# PowerSwitch_DiodeOr.net
KiCad netlist of a schematic drawn in Altium Designer
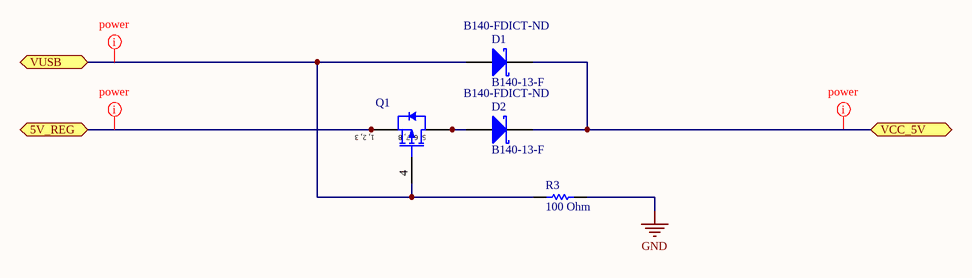
[diagram p0: PowerSwitch_DiodeOr.SchDoc]

(export (version "E")
  (design (tool "Eeschema 10.0.6"))
  (components
    (comp (ref "D1")
      (value "B140-13-F")
      (footprint "DIOD-B1X0-2_V")
      (description "Surface Mount Schottky Barrier Rectifier, 1 A, -65 to 150 degC, 2-Pin SMA, RoHS, Tape and Reel")
      (fields
        (field (name "MANUFACTURER") "DiodesIncorporated")
        (field (name "HOUSEPART") "YES")
        (field (name "SUPPLIER PART NUMBER 1") "B140-FDICT-ND")
      )
      (libsource (lib "Altium Content Vault") (part "CMP-2000-05096-1"))
    )
    (comp (ref "D2")
      (value "B140-13-F")
      (footprint "DIOD-B1X0-2_V")
      (description "Surface Mount Schottky Barrier Rectifier, 1 A, -65 to 150 degC, 2-Pin SMA, RoHS, Tape and Reel")
      (fields
        (field (name "MANUFACTURER") "DiodesIncorporated")
        (field (name "HOUSEPART") "YES")
        (field (name "SUPPLIER PART NUMBER 1") "B140-FDICT-ND")
      )
      (libsource (lib "Altium Content Vault") (part "CMP-2000-05096-1"))
    )
    (comp (ref "Q1")
      (value "SiSS23DN-T1-GE3")
      (footprint "VISH-PPAK1212-8S_V")
      (description "P-Channel MOSFET, 20 V, -50 to 150 degC, 8-Pin SMD (PPAK1212-8S), RoHS, Tape and Reel")
      (libsource (lib "Altium Content Vault") (part "CMP-1709-00001-3"))
    )
    (comp (ref "R3")
      (value "100 Ohm")
      (footprint "RESC0402(1005)_N")
      (description "100 0.063W 5% 0402 (1005 Metric)  SMD")
      (fields (field (name "TOLERANCE") "5 %") (field (name "MPN") "MF-RES-0402-10K"))
      (libsource (lib "Altium Content Vault") (part "CMP-1011-00081-1"))
    )
  )
  (nets
    (net (code "1") (name "/5V_REG") (class "Default")
      (node (ref "Q1") (pin "1") (pinfunction "S_1") (pintype "passive"))
      (node (ref "Q1") (pin "2") (pinfunction "S_2") (pintype "passive"))
      (node (ref "Q1") (pin "3") (pinfunction "S_3") (pintype "passive"))
    )
    (net (code "2") (name "/VCC_5V") (class "Default")
      (node (ref "D1") (pin "1") (pinfunction "K_1") (pintype "passive"))
      (node (ref "D2") (pin "1") (pinfunction "K_1") (pintype "passive"))
    )
    (net (code "3") (name "/VUSB") (class "Default")
      (node (ref "D1") (pin "2") (pinfunction "A_2") (pintype "passive"))
      (node (ref "Q1") (pin "4") (pinfunction "G_4") (pintype "passive"))
      (node (ref "R3") (pin "1") (pinfunction "1_1") (pintype "passive"))
    )
    (net (code "4") (name "GND") (class "Default")
      (node (ref "R3") (pin "2") (pinfunction "2_2") (pintype "passive"))
    )
    (net (code "5") (name "Net-(D2-A)") (class "Default")
      (node (ref "D2") (pin "2") (pinfunction "A_2") (pintype "passive"))
      (node (ref "Q1") (pin "5") (pinfunction "D_5") (pintype "passive"))
      (node (ref "Q1") (pin "6") (pinfunction "D_6") (pintype "passive"))
      (node (ref "Q1") (pin "7") (pinfunction "D_7") (pintype "passive"))
      (node (ref "Q1") (pin "8") (pinfunction "D_8") (pintype "passive"))
    )
  )
)
